# design.net
KiCad netlist of a schematic drawn in Altium Designer
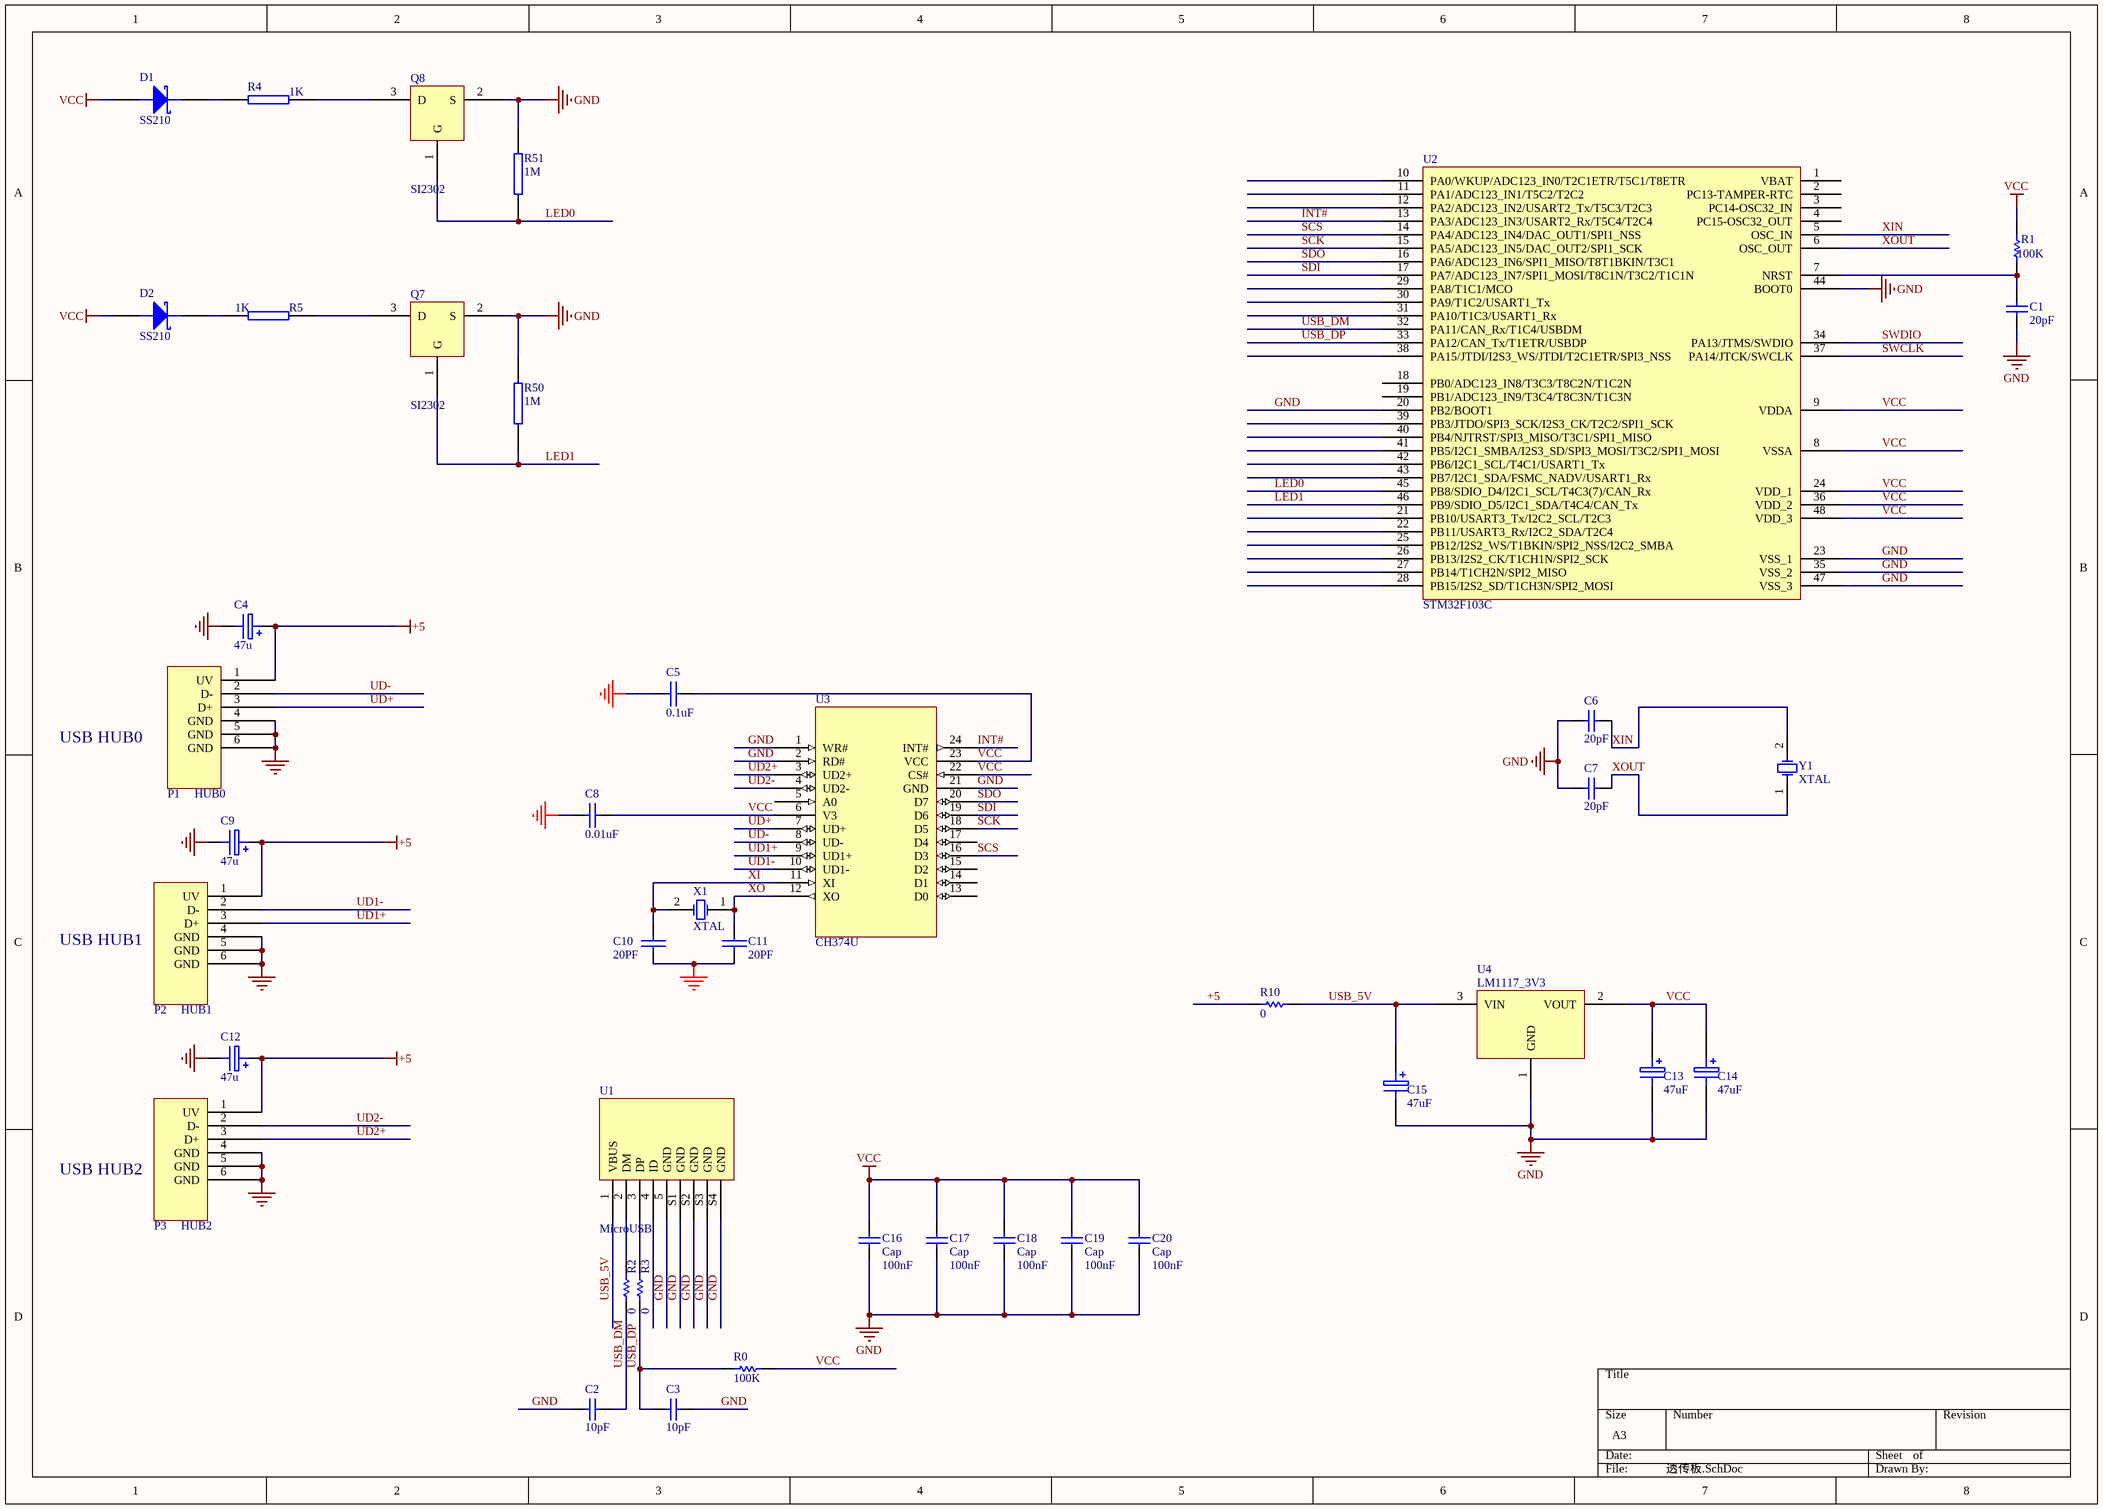
[diagram p0: 透传板.SchDoc]

(export (version "E")
  (design (tool "Eeschema 10.0.6"))
  (components
    (comp (ref "C1")
      (value "20pF")
      (footprint "0402S")
      (description "Capacitor 0402 / 0603 / 0805")
      (libsource (lib "MCD_TOOLS") (part "Capacitor_ST"))
    )
    (comp (ref "C2")
      (value "10pF")
      (footprint "0402S")
      (description "Capacitor 0402 / 0603 / 0805")
      (libsource (lib "MCD_TOOLS") (part "Capacitor_ST"))
    )
    (comp (ref "C3")
      (value "10pF")
      (footprint "0402S")
      (description "Capacitor 0402 / 0603 / 0805")
      (libsource (lib "MCD_TOOLS") (part "Capacitor_ST"))
    )
    (comp (ref "C4") (value "47u") (footprint "3216C") (libsource (lib "*") (part "CAP470U")))
    (comp (ref "C5")
      (value "0.1uF")
      (footprint "0805")
      (description "Capacitor")
      (libsource (lib "*") (part "CAP"))
    )
    (comp (ref "C6")
      (value "20pF")
      (footprint "0402S")
      (description "Capacitor 0402 / 0603 / 0805")
      (libsource (lib "MCD_TOOLS") (part "Capacitor_ST"))
    )
    (comp (ref "C7")
      (value "20pF")
      (footprint "0402S")
      (description "Capacitor 0402 / 0603 / 0805")
      (libsource (lib "MCD_TOOLS") (part "Capacitor_ST"))
    )
    (comp (ref "C8")
      (value "0.01uF")
      (footprint "0805")
      (description "Capacitor")
      (libsource (lib "*") (part "CAP"))
    )
    (comp (ref "C9") (value "47u") (footprint "3216C") (libsource (lib "*") (part "CAP470U")))
    (comp (ref "C10")
      (value "20PF")
      (footprint "0402S")
      (description "Capacitor")
      (libsource (lib "*") (part "CAP"))
    )
    (comp (ref "C11")
      (value "20PF")
      (footprint "0402S")
      (description "Capacitor")
      (libsource (lib "*") (part "CAP"))
    )
    (comp (ref "C12") (value "47u") (footprint "3216C") (libsource (lib "*") (part "CAP470U")))
    (comp (ref "C13")
      (value "47uF")
      (footprint "3216C")
      (description "Electrolytic Capacitor")
      (libsource (lib "*") (part "ELECTRO1"))
    )
    (comp (ref "C14")
      (value "47uF")
      (footprint "3216C")
      (description "Electrolytic Capacitor")
      (libsource (lib "*") (part "ELECTRO1"))
    )
    (comp (ref "C15")
      (value "47uF")
      (footprint "3216C")
      (description "Electrolytic Capacitor")
      (libsource (lib "*") (part "ELECTRO1"))
    )
    (comp (ref "C16")
      (value "Cap")
      (footprint "0402S")
      (description "Capacitor")
      (fields (field (name "ALTIUM_VALUE") "100nF") (field (name "PUBLISHER") "Altium Limited"))
      (libsource (lib "Miscellaneous Devices") (part "Cap"))
    )
    (comp (ref "C17")
      (value "Cap")
      (footprint "0402S")
      (description "Capacitor")
      (fields (field (name "ALTIUM_VALUE") "100nF") (field (name "PUBLISHER") "Altium Limited"))
      (libsource (lib "Miscellaneous Devices") (part "Cap"))
    )
    (comp (ref "C18")
      (value "Cap")
      (footprint "0402S")
      (description "Capacitor")
      (fields (field (name "ALTIUM_VALUE") "100nF") (field (name "PUBLISHER") "Altium Limited"))
      (libsource (lib "Miscellaneous Devices") (part "Cap"))
    )
    (comp (ref "C19")
      (value "Cap")
      (footprint "0402S")
      (description "Capacitor")
      (fields (field (name "ALTIUM_VALUE") "100nF") (field (name "PUBLISHER") "Altium Limited"))
      (libsource (lib "Miscellaneous Devices") (part "Cap"))
    )
    (comp (ref "C20")
      (value "Cap")
      (footprint "0402S")
      (description "Capacitor")
      (fields (field (name "ALTIUM_VALUE") "100nF") (field (name "PUBLISHER") "Altium Limited"))
      (libsource (lib "Miscellaneous Devices") (part "Cap"))
    )
    (comp (ref "D1")
      (value "SS210")
      (footprint "7227D")
      (description "Schottky Diode")
      (libsource (lib "*") (part "DIODE SCHOTTKY"))
    )
    (comp (ref "D2")
      (value "SS210")
      (footprint "7227D")
      (description "Schottky Diode")
      (libsource (lib "*") (part "DIODE SCHOTTKY"))
    )
    (comp (ref "P1") (value "USB") (footprint "USBA") (libsource (lib "*") (part "USB2")))
    (comp (ref "P2") (value "USB") (footprint "USBA") (libsource (lib "*") (part "USB2")))
    (comp (ref "P3") (value "USB") (footprint "USBA") (libsource (lib "*") (part "USB2")))
    (comp (ref "Q7") (value "SI2302") (footprint "SOT23A") (libsource (lib "STM32F405") (part "SI2302")))
    (comp (ref "Q8") (value "SI2302") (footprint "SOT23A") (libsource (lib "STM32F405") (part "SI2302")))
    (comp (ref "R0")
      (value "100K")
      (footprint "0402S")
      (description "Resistor")
      (fields (field (name "Comment") "Res1") (field (name "PUBLISHER") "Altium Limited"))
      (libsource (lib "Miscellaneous Devices") (part "Res1"))
    )
    (comp (ref "R1")
      (value "100K")
      (footprint "0402S")
      (description "Resistor")
      (fields (field (name "Comment") "Res1") (field (name "PUBLISHER") "Altium Limited"))
      (libsource (lib "Miscellaneous Devices") (part "Res1"))
    )
    (comp (ref "R2")
      (value "0")
      (footprint "0402S")
      (description "Resistor")
      (fields (field (name "Comment") "Res1") (field (name "PUBLISHER") "Altium Limited"))
      (libsource (lib "Miscellaneous Devices") (part "Res1"))
    )
    (comp (ref "R3")
      (value "0")
      (footprint "0402S")
      (description "Resistor")
      (fields (field (name "Comment") "Res1") (field (name "PUBLISHER") "Altium Limited"))
      (libsource (lib "Miscellaneous Devices") (part "Res1"))
    )
    (comp (ref "R4") (value "1K") (footprint "0805") (libsource (lib "*") (part "RES2")))
    (comp (ref "R5") (value "1K") (footprint "0805") (libsource (lib "*") (part "RES2")))
    (comp (ref "R10")
      (value "0")
      (footprint "3216C")
      (description "Resistor")
      (fields (field (name "Comment") "Res1") (field (name "PUBLISHER") "Altium Limited"))
      (libsource (lib "Miscellaneous Devices") (part "Res1"))
    )
    (comp (ref "R50") (value "1M") (footprint "0402S") (libsource (lib "*") (part "RES2")))
    (comp (ref "R51") (value "1M") (footprint "0402S") (libsource (lib "*") (part "RES2")))
    (comp (ref "U1")
      (value "MicroUSB")
      (footprint "Micro-USB")
      (libsource (lib "MicroUSB") (part "MicroUSB"))
    )
    (comp (ref "U2")
      (value "STM32F103C")
      (footprint "LQFP-48_M")
      (description "STM32单片机48引脚")
      (libsource (lib "fszhang") (part "STM32F103C"))
    )
    (comp (ref "U3") (value "CH374U") (footprint "SSOP24") (libsource (lib "*") (part "CH374U")))
    (comp (ref "U4") (value "LM1117_3V3") (footprint "SOT-223") (libsource (lib "*") (part "LM1117_3.3V")))
    (comp (ref "X1")
      (value "XTAL")
      (footprint "3225_无源")
      (description "Crystal Oscillator")
      (fields (field (name "PUBLISHER") "Altium Limited"))
      (libsource (lib "Miscellaneous Devices") (part "XTAL"))
    )
    (comp (ref "Y1")
      (value "XTAL")
      (footprint "3225_无源")
      (description "Crystal Oscillator")
      (fields (field (name "PUBLISHER") "Altium Limited"))
      (libsource (lib "Miscellaneous Devices") (part "XTAL"))
    )
  )
  (nets
    (net (code "1") (name "+5") (class "Default")
      (node (ref "C12") (pin "1") (pintype "passive"))
      (node (ref "C4") (pin "1") (pintype "passive"))
      (node (ref "C9") (pin "1") (pintype "passive"))
      (node (ref "P1") (pin "1") (pinfunction "UV_1") (pintype "passive"))
      (node (ref "P2") (pin "1") (pinfunction "UV_1") (pintype "passive"))
      (node (ref "P3") (pin "1") (pinfunction "UV_1") (pintype "passive"))
      (node (ref "R10") (pin "2") (pinfunction "2_2") (pintype "passive"))
    )
    (net (code "2") (name "/INT#") (class "Default")
      (node (ref "U2") (pin "13") (pinfunction "PA3/ADC123_IN3/USART2_Rx/T5C4/T2C4_13") (pintype "passive"))
      (node (ref "U3") (pin "24") (pinfunction "INT#_24") (pintype "output"))
    )
    (net (code "3") (name "/LED0") (class "Default")
      (node (ref "Q8") (pin "1") (pinfunction "G_1") (pintype "passive"))
      (node (ref "R51") (pin "2") (pinfunction "2_2") (pintype "passive"))
      (node (ref "U2") (pin "45") (pinfunction "PB8/SDIO_D4/I2C1_SCL/T4C3(7)/CAN_Rx_45") (pintype "passive"))
    )
    (net (code "4") (name "/LED1") (class "Default")
      (node (ref "Q7") (pin "1") (pinfunction "G_1") (pintype "passive"))
      (node (ref "R50") (pin "2") (pinfunction "2_2") (pintype "passive"))
      (node (ref "U2") (pin "46") (pinfunction "PB9/SDIO_D5/I2C1_SDA/T4C4/CAN_Tx_46") (pintype "passive"))
    )
    (net (code "5") (name "/SCK") (class "Default")
      (node (ref "U2") (pin "15") (pinfunction "PA5/ADC123_IN5/DAC_OUT2/SPI1_SCK_15") (pintype "passive"))
      (node (ref "U3") (pin "18") (pinfunction "D5_18") (pintype "bidirectional"))
    )
    (net (code "6") (name "/SCS") (class "Default")
      (node (ref "U2") (pin "14") (pinfunction "PA4/ADC123_IN4/DAC_OUT1/SPI1_NSS_14") (pintype "passive"))
      (node (ref "U3") (pin "16") (pinfunction "D3_16") (pintype "bidirectional"))
    )
    (net (code "7") (name "/SDI") (class "Default")
      (node (ref "U2") (pin "17") (pinfunction "PA7/ADC123_IN7/SPI1_MOSI/T8C1N/T3C2/T1C1N_17") (pintype "passive"))
      (node (ref "U3") (pin "19") (pinfunction "D6_19") (pintype "bidirectional"))
    )
    (net (code "8") (name "/SDO") (class "Default")
      (node (ref "U2") (pin "16") (pinfunction "PA6/ADC123_IN6/SPI1_MISO/T8T1BKIN/T3C1_16") (pintype "passive"))
      (node (ref "U3") (pin "20") (pinfunction "D7_20") (pintype "bidirectional"))
    )
    (net (code "9") (name "/SWCLK") (class "Default")
      (node (ref "U2") (pin "37") (pinfunction "PA14/JTCK/SWCLK_37") (pintype "passive"))
    )
    (net (code "10") (name "/SWDIO") (class "Default")
      (node (ref "U2") (pin "34") (pinfunction "PA13/JTMS/SWDIO_34") (pintype "passive"))
    )
    (net (code "11") (name "/UD+") (class "Default")
      (node (ref "P1") (pin "3") (pinfunction "D+_3") (pintype "passive"))
      (node (ref "U3") (pin "7") (pinfunction "UD+_7") (pintype "bidirectional"))
    )
    (net (code "12") (name "/UD-") (class "Default")
      (node (ref "P1") (pin "2") (pinfunction "D-_2") (pintype "passive"))
      (node (ref "U3") (pin "8") (pinfunction "UD-_8") (pintype "bidirectional"))
    )
    (net (code "13") (name "/UD1+") (class "Default")
      (node (ref "P2") (pin "3") (pinfunction "D+_3") (pintype "passive"))
      (node (ref "U3") (pin "9") (pinfunction "UD1+_9") (pintype "bidirectional"))
    )
    (net (code "14") (name "/UD1-") (class "Default")
      (node (ref "P2") (pin "2") (pinfunction "D-_2") (pintype "passive"))
      (node (ref "U3") (pin "10") (pinfunction "UD1-_10") (pintype "bidirectional"))
    )
    (net (code "15") (name "/UD2+") (class "Default")
      (node (ref "P3") (pin "3") (pinfunction "D+_3") (pintype "passive"))
      (node (ref "U3") (pin "3") (pinfunction "UD2+_3") (pintype "bidirectional"))
    )
    (net (code "16") (name "/UD2-") (class "Default")
      (node (ref "P3") (pin "2") (pinfunction "D-_2") (pintype "passive"))
      (node (ref "U3") (pin "4") (pinfunction "UD2-_4") (pintype "bidirectional"))
    )
    (net (code "17") (name "/USB_5V") (class "Default")
      (node (ref "C15") (pin "1") (pinfunction "1_1") (pintype "passive"))
      (node (ref "R10") (pin "1") (pinfunction "1_1") (pintype "passive"))
      (node (ref "U1") (pin "1") (pinfunction "VBUS_1") (pintype "passive"))
      (node (ref "U4") (pin "3") (pinfunction "VIN_3") (pintype "passive"))
    )
    (net (code "18") (name "/USB_DM") (class "Default")
      (node (ref "C2") (pin "1") (pinfunction "1_1") (pintype "passive"))
      (node (ref "R2") (pin "2") (pinfunction "2_2") (pintype "passive"))
      (node (ref "U2") (pin "32") (pinfunction "PA11/CAN_Rx/T1C4/USBDM_32") (pintype "passive"))
    )
    (net (code "19") (name "/USB_DP") (class "Default")
      (node (ref "C3") (pin "1") (pinfunction "1_1") (pintype "passive"))
      (node (ref "R0") (pin "2") (pinfunction "2_2") (pintype "passive"))
      (node (ref "R3") (pin "2") (pinfunction "2_2") (pintype "passive"))
      (node (ref "U2") (pin "33") (pinfunction "PA12/CAN_Tx/T1ETR/USBDP_33") (pintype "passive"))
    )
    (net (code "20") (name "/XI") (class "Default")
      (node (ref "C10") (pin "1") (pinfunction "1_1") (pintype "passive"))
      (node (ref "U3") (pin "11") (pinfunction "XI_11") (pintype "input"))
      (node (ref "X1") (pin "2") (pinfunction "OSC2_2") (pintype "passive"))
    )
    (net (code "21") (name "/XIN") (class "Default")
      (node (ref "C6") (pin "1") (pinfunction "1_1") (pintype "passive"))
      (node (ref "U2") (pin "5") (pinfunction "OSC_IN_5") (pintype "passive"))
      (node (ref "Y1") (pin "2") (pinfunction "OSC2_2") (pintype "passive"))
    )
    (net (code "22") (name "/XO") (class "Default")
      (node (ref "C11") (pin "1") (pinfunction "1_1") (pintype "passive"))
      (node (ref "U3") (pin "12") (pinfunction "XO_12") (pintype "output"))
      (node (ref "X1") (pin "1") (pinfunction "OSC1_1") (pintype "passive"))
    )
    (net (code "23") (name "/XOUT") (class "Default")
      (node (ref "C7") (pin "1") (pinfunction "1_1") (pintype "passive"))
      (node (ref "U2") (pin "6") (pinfunction "OSC_OUT_6") (pintype "passive"))
      (node (ref "Y1") (pin "1") (pinfunction "OSC1_1") (pintype "passive"))
    )
    (net (code "24") (name "GND") (class "Default")
      (node (ref "C1") (pin "2") (pinfunction "2_2") (pintype "passive"))
      (node (ref "C10") (pin "2") (pinfunction "2_2") (pintype "passive"))
      (node (ref "C11") (pin "2") (pinfunction "2_2") (pintype "passive"))
      (node (ref "C12") (pin "2") (pintype "passive"))
      (node (ref "C13") (pin "2") (pinfunction "2_2") (pintype "passive"))
      (node (ref "C14") (pin "2") (pinfunction "2_2") (pintype "passive"))
      (node (ref "C15") (pin "2") (pinfunction "2_2") (pintype "passive"))
      (node (ref "C16") (pin "1") (pinfunction "1_1") (pintype "passive"))
      (node (ref "C17") (pin "1") (pinfunction "1_1") (pintype "passive"))
      (node (ref "C18") (pin "1") (pinfunction "1_1") (pintype "passive"))
      (node (ref "C19") (pin "1") (pinfunction "1_1") (pintype "passive"))
      (node (ref "C2") (pin "2") (pinfunction "2_2") (pintype "passive"))
      (node (ref "C20") (pin "1") (pinfunction "1_1") (pintype "passive"))
      (node (ref "C3") (pin "2") (pinfunction "2_2") (pintype "passive"))
      (node (ref "C4") (pin "2") (pintype "passive"))
      (node (ref "C5") (pin "2") (pinfunction "2_2") (pintype "passive"))
      (node (ref "C6") (pin "2") (pinfunction "2_2") (pintype "passive"))
      (node (ref "C7") (pin "2") (pinfunction "2_2") (pintype "passive"))
      (node (ref "C8") (pin "2") (pinfunction "2_2") (pintype "passive"))
      (node (ref "C9") (pin "2") (pintype "passive"))
      (node (ref "P1") (pin "4") (pinfunction "GND_4") (pintype "passive"))
      (node (ref "P1") (pin "5") (pinfunction "GND_5") (pintype "passive"))
      (node (ref "P1") (pin "6") (pinfunction "GND_6") (pintype "passive"))
      (node (ref "P2") (pin "4") (pinfunction "GND_4") (pintype "passive"))
      (node (ref "P2") (pin "5") (pinfunction "GND_5") (pintype "passive"))
      (node (ref "P2") (pin "6") (pinfunction "GND_6") (pintype "passive"))
      (node (ref "P3") (pin "4") (pinfunction "GND_4") (pintype "passive"))
      (node (ref "P3") (pin "5") (pinfunction "GND_5") (pintype "passive"))
      (node (ref "P3") (pin "6") (pinfunction "GND_6") (pintype "passive"))
      (node (ref "Q7") (pin "2") (pinfunction "S_2") (pintype "passive"))
      (node (ref "Q8") (pin "2") (pinfunction "S_2") (pintype "passive"))
      (node (ref "R50") (pin "1") (pinfunction "1_1") (pintype "passive"))
      (node (ref "R51") (pin "1") (pinfunction "1_1") (pintype "passive"))
      (node (ref "U1") (pin "5") (pinfunction "GND_5") (pintype "passive"))
      (node (ref "U1") (pin "S1") (pinfunction "GND_S1") (pintype "passive"))
      (node (ref "U1") (pin "S2") (pinfunction "GND_S2") (pintype "passive"))
      (node (ref "U1") (pin "S3") (pinfunction "GND_S3") (pintype "passive"))
      (node (ref "U1") (pin "S4") (pinfunction "GND_S4") (pintype "passive"))
      (node (ref "U2") (pin "20") (pinfunction "PB2/BOOT1_20") (pintype "passive"))
      (node (ref "U2") (pin "23") (pinfunction "VSS_1_23") (pintype "passive"))
      (node (ref "U2") (pin "35") (pinfunction "VSS_2_35") (pintype "passive"))
      (node (ref "U2") (pin "44") (pinfunction "BOOT0_44") (pintype "passive"))
      (node (ref "U2") (pin "47") (pinfunction "VSS_3_47") (pintype "passive"))
      (node (ref "U3") (pin "1") (pinfunction "WR#_1") (pintype "input"))
      (node (ref "U3") (pin "2") (pinfunction "RD#_2") (pintype "input"))
      (node (ref "U3") (pin "21") (pinfunction "GND_21") (pintype "power_in"))
      (node (ref "U4") (pin "1") (pinfunction "GND_1") (pintype "passive"))
    )
    (net (code "25") (name "Net-(D1-K)") (class "Default")
      (node (ref "D1") (pin "2") (pinfunction "K_2") (pintype "passive"))
      (node (ref "R4") (pin "2") (pinfunction "2_2") (pintype "passive"))
    )
    (net (code "26") (name "Net-(D2-K)") (class "Default")
      (node (ref "D2") (pin "2") (pinfunction "K_2") (pintype "passive"))
      (node (ref "R5") (pin "2") (pinfunction "2_2") (pintype "passive"))
    )
    (net (code "27") (name "Net-(Q7-D)") (class "Default")
      (node (ref "Q7") (pin "3") (pinfunction "D_3") (pintype "passive"))
      (node (ref "R5") (pin "1") (pinfunction "1_1") (pintype "passive"))
    )
    (net (code "28") (name "Net-(Q8-D)") (class "Default")
      (node (ref "Q8") (pin "3") (pinfunction "D_3") (pintype "passive"))
      (node (ref "R4") (pin "1") (pinfunction "1_1") (pintype "passive"))
    )
    (net (code "29") (name "Net-(U1-DM)") (class "Default")
      (node (ref "R2") (pin "1") (pinfunction "1_1") (pintype "passive"))
      (node (ref "U1") (pin "2") (pinfunction "DM_2") (pintype "passive"))
    )
    (net (code "30") (name "Net-(U1-DP)") (class "Default")
      (node (ref "R3") (pin "1") (pinfunction "1_1") (pintype "passive"))
      (node (ref "U1") (pin "3") (pinfunction "DP_3") (pintype "passive"))
    )
    (net (code "31") (name "Net-(U2-NRST)") (class "Default")
      (node (ref "C1") (pin "1") (pinfunction "1_1") (pintype "passive"))
      (node (ref "R1") (pin "1") (pinfunction "1_1") (pintype "passive"))
      (node (ref "U2") (pin "7") (pinfunction "NRST_7") (pintype "passive"))
    )
    (net (code "32") (name "VCC") (class "Default")
      (node (ref "C13") (pin "1") (pinfunction "1_1") (pintype "passive"))
      (node (ref "C14") (pin "1") (pinfunction "1_1") (pintype "passive"))
      (node (ref "C16") (pin "2") (pinfunction "2_2") (pintype "passive"))
      (node (ref "C17") (pin "2") (pinfunction "2_2") (pintype "passive"))
      (node (ref "C18") (pin "2") (pinfunction "2_2") (pintype "passive"))
      (node (ref "C19") (pin "2") (pinfunction "2_2") (pintype "passive"))
      (node (ref "C20") (pin "2") (pinfunction "2_2") (pintype "passive"))
      (node (ref "C5") (pin "1") (pinfunction "1_1") (pintype "passive"))
      (node (ref "C8") (pin "1") (pinfunction "1_1") (pintype "passive"))
      (node (ref "D1") (pin "1") (pinfunction "A_1") (pintype "passive"))
      (node (ref "D2") (pin "1") (pinfunction "A_1") (pintype "passive"))
      (node (ref "R0") (pin "1") (pinfunction "1_1") (pintype "passive"))
      (node (ref "R1") (pin "2") (pinfunction "2_2") (pintype "passive"))
      (node (ref "U2") (pin "24") (pinfunction "VDD_1_24") (pintype "passive"))
      (node (ref "U2") (pin "36") (pinfunction "VDD_2_36") (pintype "passive"))
      (node (ref "U2") (pin "48") (pinfunction "VDD_3_48") (pintype "passive"))
      (node (ref "U2") (pin "8") (pinfunction "VSSA_8") (pintype "passive"))
      (node (ref "U2") (pin "9") (pinfunction "VDDA_9") (pintype "passive"))
      (node (ref "U3") (pin "22") (pinfunction "CS#_22") (pintype "input"))
      (node (ref "U3") (pin "23") (pinfunction "VCC_23") (pintype "power_in"))
      (node (ref "U3") (pin "6") (pinfunction "V3_6") (pintype "power_in"))
      (node (ref "U4") (pin "2") (pinfunction "VOUT_2") (pintype "passive"))
    )
    (net (code "33") (name "unconnected-(U1-ID-Pad4)") (class "Default")
      (node (ref "U1") (pin "4") (pinfunction "ID_4") (pintype "passive"))
    )
    (net (code "34") (name "unconnected-(U2-PA0{slash}WKUP{slash}ADC123_IN0{slash}T2C1ETR{slash}T5C1{slash}T8ETR-Pad10)") (class "Default")
      (node (ref "U2") (pin "10") (pinfunction "PA0/WKUP/ADC123_IN0/T2C1ETR/T5C1/T8ETR_10") (pintype "passive"))
    )
    (net (code "35") (name "unconnected-(U2-PA1{slash}ADC123_IN1{slash}T5C2{slash}T2C2-Pad11)") (class "Default")
      (node (ref "U2") (pin "11") (pinfunction "PA1/ADC123_IN1/T5C2/T2C2_11") (pintype "passive"))
    )
    (net (code "36") (name "unconnected-(U2-PA2{slash}ADC123_IN2{slash}USART2_Tx{slash}T5C3{slash}T2C3-Pad12)") (class "Default")
      (node (ref "U2") (pin "12") (pinfunction "PA2/ADC123_IN2/USART2_Tx/T5C3/T2C3_12") (pintype "passive"))
    )
    (net (code "37") (name "unconnected-(U2-PA8{slash}T1C1{slash}MCO-Pad29)") (class "Default")
      (node (ref "U2") (pin "29") (pinfunction "PA8/T1C1/MCO_29") (pintype "passive"))
    )
    (net (code "38") (name "unconnected-(U2-PA9{slash}T1C2{slash}USART1_Tx-Pad30)") (class "Default")
      (node (ref "U2") (pin "30") (pinfunction "PA9/T1C2/USART1_Tx_30") (pintype "passive"))
    )
    (net (code "39") (name "unconnected-(U2-PA10{slash}T1C3{slash}USART1_Rx-Pad31)") (class "Default")
      (node (ref "U2") (pin "31") (pinfunction "PA10/T1C3/USART1_Rx_31") (pintype "passive"))
    )
    (net (code "40") (name "unconnected-(U2-PA15{slash}JTDI{slash}I2S3_WS{slash}JTDI{slash}T2C1ETR{slash}SPI3_NSS-Pad38)") (class "Default")
      (node (ref "U2") (pin "38") (pinfunction "PA15/JTDI/I2S3_WS/JTDI/T2C1ETR/SPI3_NSS_38") (pintype "passive"))
    )
    (net (code "41") (name "unconnected-(U2-PB0{slash}ADC123_IN8{slash}T3C3{slash}T8C2N{slash}T1C2N-Pad18)") (class "Default")
      (node (ref "U2") (pin "18") (pinfunction "PB0/ADC123_IN8/T3C3/T8C2N/T1C2N_18") (pintype "passive"))
    )
    (net (code "42") (name "unconnected-(U2-PB1{slash}ADC123_IN9{slash}T3C4{slash}T8C3N{slash}T1C3N-Pad19)") (class "Default")
      (node (ref "U2") (pin "19") (pinfunction "PB1/ADC123_IN9/T3C4/T8C3N/T1C3N_19") (pintype "passive"))
    )
    (net (code "43") (name "unconnected-(U2-PB3{slash}JTDO{slash}SPI3_SCK{slash}I2S3_CK{slash}T2C2{slash}SPI1_SCK-Pad39)") (class "Default")
      (node (ref "U2") (pin "39") (pinfunction "PB3/JTDO/SPI3_SCK/I2S3_CK/T2C2/SPI1_SCK_39") (pintype "passive"))
    )
    (net (code "44") (name "unconnected-(U2-PB4{slash}NJTRST{slash}SPI3_MISO{slash}T3C1{slash}SPI1_MISO-Pad40)") (class "Default")
      (node (ref "U2") (pin "40") (pinfunction "PB4/NJTRST/SPI3_MISO/T3C1/SPI1_MISO_40") (pintype "passive"))
    )
    (net (code "45") (name "unconnected-(U2-PB5{slash}I2C1_SMBA{slash}I2S3_SD{slash}SPI3_MOSI{slash}T3C2{slash}SPI1_MOSI-Pad41)") (class "Default")
      (node (ref "U2") (pin "41") (pinfunction "PB5/I2C1_SMBA/I2S3_SD/SPI3_MOSI/T3C2/SPI1_MOSI_41") (pintype "passive"))
    )
    (net (code "46") (name "unconnected-(U2-PB6{slash}I2C1_SCL{slash}T4C1{slash}USART1_Tx-Pad42)") (class "Default")
      (node (ref "U2") (pin "42") (pinfunction "PB6/I2C1_SCL/T4C1/USART1_Tx_42") (pintype "passive"))
    )
    (net (code "47") (name "unconnected-(U2-PB7{slash}I2C1_SDA{slash}FSMC_NADV{slash}USART1_Rx-Pad43)") (class "Default")
      (node (ref "U2") (pin "43") (pinfunction "PB7/I2C1_SDA/FSMC_NADV/USART1_Rx_43") (pintype "passive"))
    )
    (net (code "48") (name "unconnected-(U2-PB10{slash}USART3_Tx{slash}I2C2_SCL{slash}T2C3-Pad21)") (class "Default")
      (node (ref "U2") (pin "21") (pinfunction "PB10/USART3_Tx/I2C2_SCL/T2C3_21") (pintype "passive"))
    )
    (net (code "49") (name "unconnected-(U2-PB11{slash}USART3_Rx{slash}I2C2_SDA{slash}T2C4-Pad22)") (class "Default")
      (node (ref "U2") (pin "22") (pinfunction "PB11/USART3_Rx/I2C2_SDA/T2C4_22") (pintype "passive"))
    )
    (net (code "50") (name "unconnected-(U2-PB12{slash}I2S2_WS{slash}T1BKIN{slash}SPI2_NSS{slash}I2C2_SMBA-Pad25)") (class "Default")
      (node (ref "U2") (pin "25") (pinfunction "PB12/I2S2_WS/T1BKIN/SPI2_NSS/I2C2_SMBA_25") (pintype "passive"))
    )
    (net (code "51") (name "unconnected-(U2-PB13{slash}I2S2_CK{slash}T1CH1N{slash}SPI2_SCK-Pad26)") (class "Default")
      (node (ref "U2") (pin "26") (pinfunction "PB13/I2S2_CK/T1CH1N/SPI2_SCK_26") (pintype "passive"))
    )
    (net (code "52") (name "unconnected-(U2-PB14{slash}T1CH2N{slash}SPI2_MISO-Pad27)") (class "Default")
      (node (ref "U2") (pin "27") (pinfunction "PB14/T1CH2N/SPI2_MISO_27") (pintype "passive"))
    )
    (net (code "53") (name "unconnected-(U2-PB15{slash}I2S2_SD{slash}T1CH3N{slash}SPI2_MOSI-Pad28)") (class "Default")
      (node (ref "U2") (pin "28") (pinfunction "PB15/I2S2_SD/T1CH3N/SPI2_MOSI_28") (pintype "passive"))
    )
    (net (code "54") (name "unconnected-(U2-PC13-TAMPER-RTC-Pad2)") (class "Default")
      (node (ref "U2") (pin "2") (pinfunction "PC13-TAMPER-RTC_2") (pintype "passive"))
    )
    (net (code "55") (name "unconnected-(U2-PC14-OSC32_IN-Pad3)") (class "Default")
      (node (ref "U2") (pin "3") (pinfunction "PC14-OSC32_IN_3") (pintype "passive"))
    )
    (net (code "56") (name "unconnected-(U2-PC15-OSC32_OUT-Pad4)") (class "Default")
      (node (ref "U2") (pin "4") (pinfunction "PC15-OSC32_OUT_4") (pintype "passive"))
    )
    (net (code "57") (name "unconnected-(U2-VBAT-Pad1)") (class "Default")
      (node (ref "U2") (pin "1") (pinfunction "VBAT_1") (pintype "passive"))
    )
    (net (code "58") (name "unconnected-(U3-A0-Pad5)") (class "Default")
      (node (ref "U3") (pin "5") (pinfunction "A0_5") (pintype "input"))
    )
    (net (code "59") (name "unconnected-(U3-D0-Pad13)") (class "Default")
      (node (ref "U3") (pin "13") (pinfunction "D0_13") (pintype "bidirectional"))
    )
    (net (code "60") (name "unconnected-(U3-D1-Pad14)") (class "Default")
      (node (ref "U3") (pin "14") (pinfunction "D1_14") (pintype "bidirectional"))
    )
    (net (code "61") (name "unconnected-(U3-D2-Pad15)") (class "Default")
      (node (ref "U3") (pin "15") (pinfunction "D2_15") (pintype "bidirectional"))
    )
    (net (code "62") (name "unconnected-(U3-D4-Pad17)") (class "Default")
      (node (ref "U3") (pin "17") (pinfunction "D4_17") (pintype "bidirectional"))
    )
  )
)
